# GBA_Wireless_Gamepad.net
KiCad netlist of a schematic drawn in EAGLE
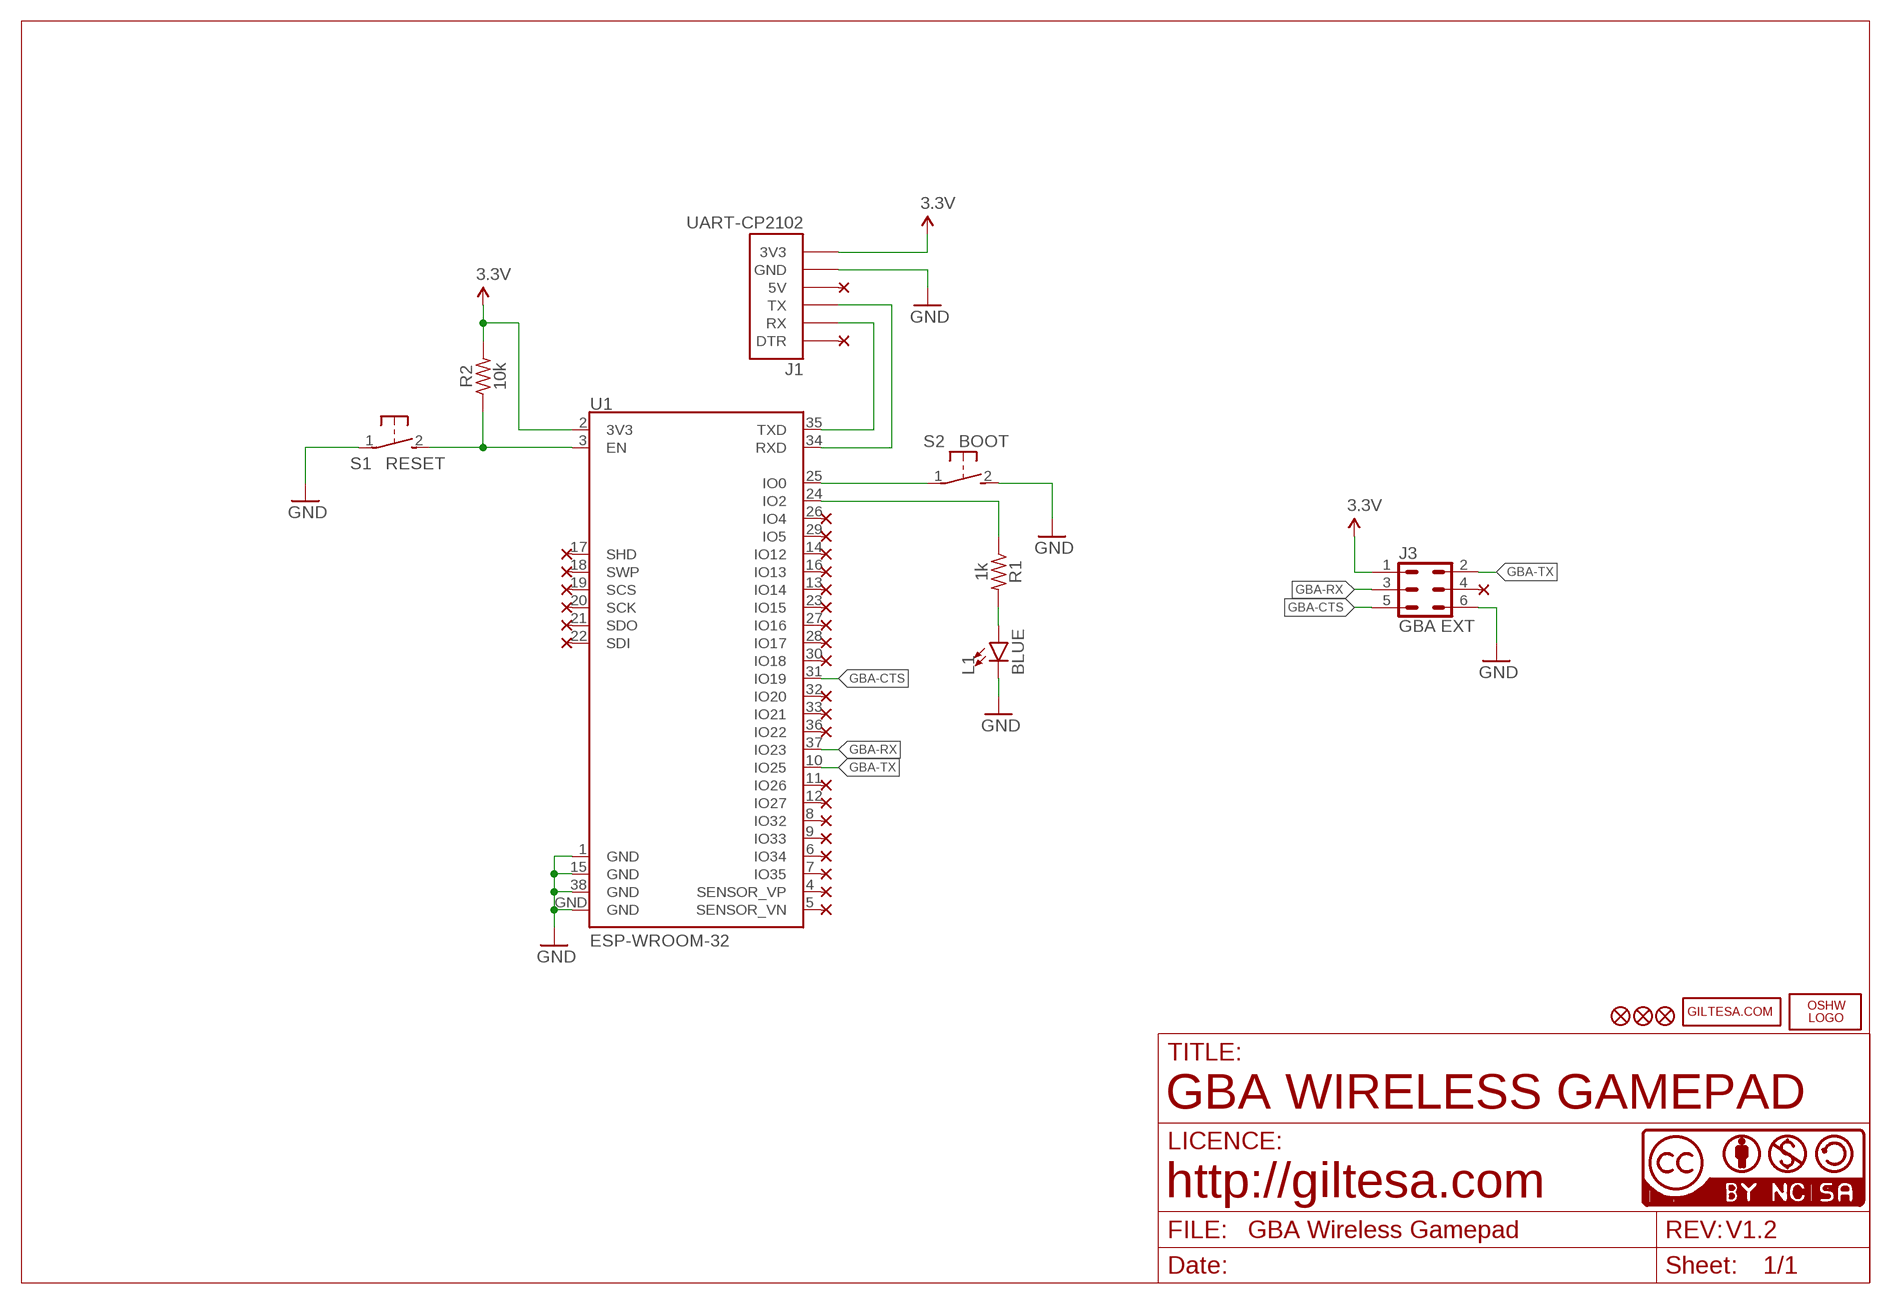
[diagram p0: schematic, sheet 1]

(export (version "E")
  (design (tool "Eeschema 10.0.6"))
  (components
    (comp (ref "J1")
      (value "UART-CP2102")
      (footprint "eagle-import:UART-CP2102")
      (libsource (lib "eagle-import") (part "UART-CP2102"))
    )
    (comp (ref "J3")
      (value "GBA EXT")
      (footprint "eagle-import:GBA_EXT")
      (libsource (lib "eagle-import") (part "GBA_EXT"))
    )
    (comp (ref "L1")
      (value "BLUE")
      (footprint "eagle-import:LED-0603")
      (libsource (lib "eagle-import") (part "LED-BLUE0603"))
    )
    (comp (ref "LOGO1")
      (value "OSHW_LOGO_FILLX0150-NT")
      (footprint "eagle-import:OSHW_FILLX150_NOTEXT")
      (libsource (lib "eagle-import") (part "OSHW_LOGO_FILLX0150-NT"))
    )
    (comp (ref "R1")
      (value "1k")
      (footprint "eagle-import:R0603")
      (libsource (lib "eagle-import") (part "R0603"))
    )
    (comp (ref "R2")
      (value "10k")
      (footprint "eagle-import:R0603")
      (libsource (lib "eagle-import") (part "R0603"))
    )
    (comp (ref "S1")
      (value "RESET")
      (footprint "eagle-import:SWITCH_SMD_4.6X2.8MM")
      (libsource (lib "eagle-import") (part "SWITCH_2P4.6X2.8MM"))
    )
    (comp (ref "S2")
      (value "BOOT")
      (footprint "eagle-import:SWITCH_SMD_4.6X2.8MM")
      (libsource (lib "eagle-import") (part "SWITCH_2P4.6X2.8MM"))
    )
    (comp (ref "U$6")
      (value "FIDUCIAL1X2")
      (footprint "eagle-import:FIDUCIAL-1X2")
      (libsource (lib "eagle-import") (part "FIDUCIAL1X2"))
    )
    (comp (ref "U$7")
      (value "FIDUCIAL1X2")
      (footprint "eagle-import:FIDUCIAL-1X2")
      (libsource (lib "eagle-import") (part "FIDUCIAL1X2"))
    )
    (comp (ref "U$10")
      (value "GILTESA.COM_MASK")
      (footprint "eagle-import:GILTESA.COM_MASK_15MM")
      (libsource (lib "eagle-import") (part "GILTESA.COM_MASK"))
    )
    (comp (ref "U$14")
      (value "FIDUCIAL1X2")
      (footprint "eagle-import:FIDUCIAL-1X2")
      (libsource (lib "eagle-import") (part "FIDUCIAL1X2"))
    )
    (comp (ref "U$17")
      (value "CC-NC-BCNIX")
      (footprint "eagle-import:CC-NC-B_NIX")
      (libsource (lib "eagle-import") (part "CC-NC-BCNIX"))
    )
    (comp (ref "U1")
      (value "ESP-WROOM-32")
      (footprint "eagle-import:ESP32-WROOM-NARROW")
      (libsource (lib "eagle-import") (part "ESP32-WROOMNARROW"))
    )
  )
  (nets
    (net (code "1") (name "3.3V") (class "Default")
      (node (ref "J1") (pin "3V3") (pinfunction "3V3_3V3") (pintype "bidirectional"))
      (node (ref "J3") (pin "1") (pinfunction "1_1") (pintype "passive"))
      (node (ref "R2") (pin "2") (pinfunction "2_2") (pintype "passive"))
      (node (ref "U1") (pin "2") (pinfunction "3V3_2") (pintype "bidirectional"))
    )
    (net (code "2") (name "GBA-CTS") (class "Default")
      (node (ref "J3") (pin "5") (pinfunction "5_5") (pintype "passive"))
      (node (ref "U1") (pin "31") (pinfunction "IO19_31") (pintype "bidirectional"))
    )
    (net (code "3") (name "GBA-RX") (class "Default")
      (node (ref "J3") (pin "3") (pinfunction "3_3") (pintype "passive"))
      (node (ref "U1") (pin "37") (pinfunction "IO23_37") (pintype "bidirectional"))
    )
    (net (code "4") (name "GBA-TX") (class "Default")
      (node (ref "J3") (pin "2") (pinfunction "2_2") (pintype "passive"))
      (node (ref "U1") (pin "10") (pinfunction "IO25_10") (pintype "bidirectional"))
    )
    (net (code "5") (name "GND") (class "Default")
      (node (ref "J1") (pin "GND") (pinfunction "GND_GND") (pintype "bidirectional"))
      (node (ref "J3") (pin "6") (pinfunction "6_6") (pintype "passive"))
      (node (ref "L1") (pin "C") (pinfunction "C_C") (pintype "passive"))
      (node (ref "S1") (pin "1") (pinfunction "A_1") (pintype "passive"))
      (node (ref "S2") (pin "2") (pinfunction "B_2") (pintype "passive"))
      (node (ref "U1") (pin "1") (pinfunction "GND_1") (pintype "bidirectional"))
      (node (ref "U1") (pin "15") (pinfunction "GND_15") (pintype "bidirectional"))
      (node (ref "U1") (pin "38") (pinfunction "GND_38") (pintype "bidirectional"))
      (node (ref "U1") (pin "GND") (pinfunction "GND_GND") (pintype "bidirectional"))
    )
    (net (code "6") (name "Net-(L1-PadA)") (class "Default")
      (node (ref "L1") (pin "A") (pinfunction "A_A") (pintype "passive"))
      (node (ref "R1") (pin "2") (pinfunction "2_2") (pintype "passive"))
    )
    (net (code "7") (name "Net-(S1-B)") (class "Default")
      (node (ref "R2") (pin "1") (pinfunction "1_1") (pintype "passive"))
      (node (ref "S1") (pin "2") (pinfunction "B_2") (pintype "passive"))
      (node (ref "U1") (pin "3") (pinfunction "EN_3") (pintype "bidirectional"))
    )
    (net (code "8") (name "Net-(S2-A)") (class "Default")
      (node (ref "S2") (pin "1") (pinfunction "A_1") (pintype "passive"))
      (node (ref "U1") (pin "25") (pinfunction "IO0_25") (pintype "bidirectional"))
    )
    (net (code "9") (name "Net-(U1-IO2)") (class "Default")
      (node (ref "R1") (pin "1") (pinfunction "1_1") (pintype "passive"))
      (node (ref "U1") (pin "24") (pinfunction "IO2_24") (pintype "bidirectional"))
    )
    (net (code "10") (name "Net-(U1-RXD)") (class "Default")
      (node (ref "J1") (pin "TX") (pinfunction "TX_TX") (pintype "bidirectional"))
      (node (ref "U1") (pin "34") (pinfunction "RXD_34") (pintype "bidirectional"))
    )
    (net (code "11") (name "Net-(U1-TXD)") (class "Default")
      (node (ref "J1") (pin "RX") (pinfunction "RX_RX") (pintype "bidirectional"))
      (node (ref "U1") (pin "35") (pinfunction "TXD_35") (pintype "bidirectional"))
    )
    (net (code "12") (name "unconnected-(J1-Pad5V)") (class "Default")
      (node (ref "J1") (pin "5V") (pinfunction "5V_5V") (pintype "bidirectional"))
    )
    (net (code "13") (name "unconnected-(J1-PadDTR)") (class "Default")
      (node (ref "J1") (pin "DTR") (pinfunction "DTR_DTR") (pintype "bidirectional"))
    )
    (net (code "14") (name "unconnected-(J3-Pad4)") (class "Default")
      (node (ref "J3") (pin "4") (pinfunction "4_4") (pintype "passive"))
    )
    (net (code "15") (name "unconnected-(U1-IO4-Pad26)") (class "Default")
      (node (ref "U1") (pin "26") (pinfunction "IO4_26") (pintype "bidirectional"))
    )
    (net (code "16") (name "unconnected-(U1-IO5-Pad29)") (class "Default")
      (node (ref "U1") (pin "29") (pinfunction "IO5_29") (pintype "bidirectional"))
    )
    (net (code "17") (name "unconnected-(U1-IO12-Pad14)") (class "Default")
      (node (ref "U1") (pin "14") (pinfunction "IO12_14") (pintype "bidirectional"))
    )
    (net (code "18") (name "unconnected-(U1-IO13-Pad16)") (class "Default")
      (node (ref "U1") (pin "16") (pinfunction "IO13_16") (pintype "bidirectional"))
    )
    (net (code "19") (name "unconnected-(U1-IO14-Pad13)") (class "Default")
      (node (ref "U1") (pin "13") (pinfunction "IO14_13") (pintype "bidirectional"))
    )
    (net (code "20") (name "unconnected-(U1-IO15-Pad23)") (class "Default")
      (node (ref "U1") (pin "23") (pinfunction "IO15_23") (pintype "bidirectional"))
    )
    (net (code "21") (name "unconnected-(U1-IO16-Pad27)") (class "Default")
      (node (ref "U1") (pin "27") (pinfunction "IO16_27") (pintype "bidirectional"))
    )
    (net (code "22") (name "unconnected-(U1-IO17-Pad28)") (class "Default")
      (node (ref "U1") (pin "28") (pinfunction "IO17_28") (pintype "bidirectional"))
    )
    (net (code "23") (name "unconnected-(U1-IO18-Pad30)") (class "Default")
      (node (ref "U1") (pin "30") (pinfunction "IO18_30") (pintype "bidirectional"))
    )
    (net (code "24") (name "unconnected-(U1-IO20-Pad32)") (class "Default")
      (node (ref "U1") (pin "32") (pinfunction "IO20_32") (pintype "bidirectional"))
    )
    (net (code "25") (name "unconnected-(U1-IO21-Pad33)") (class "Default")
      (node (ref "U1") (pin "33") (pinfunction "IO21_33") (pintype "bidirectional"))
    )
    (net (code "26") (name "unconnected-(U1-IO22-Pad36)") (class "Default")
      (node (ref "U1") (pin "36") (pinfunction "IO22_36") (pintype "bidirectional"))
    )
    (net (code "27") (name "unconnected-(U1-IO26-Pad11)") (class "Default")
      (node (ref "U1") (pin "11") (pinfunction "IO26_11") (pintype "bidirectional"))
    )
    (net (code "28") (name "unconnected-(U1-IO27-Pad12)") (class "Default")
      (node (ref "U1") (pin "12") (pinfunction "IO27_12") (pintype "bidirectional"))
    )
    (net (code "29") (name "unconnected-(U1-IO32-Pad8)") (class "Default")
      (node (ref "U1") (pin "8") (pinfunction "IO32_8") (pintype "bidirectional"))
    )
    (net (code "30") (name "unconnected-(U1-IO33-Pad9)") (class "Default")
      (node (ref "U1") (pin "9") (pinfunction "IO33_9") (pintype "bidirectional"))
    )
    (net (code "31") (name "unconnected-(U1-IO34-Pad6)") (class "Default")
      (node (ref "U1") (pin "6") (pinfunction "IO34_6") (pintype "bidirectional"))
    )
    (net (code "32") (name "unconnected-(U1-IO35-Pad7)") (class "Default")
      (node (ref "U1") (pin "7") (pinfunction "IO35_7") (pintype "bidirectional"))
    )
    (net (code "33") (name "unconnected-(U1-SCK-Pad20)") (class "Default")
      (node (ref "U1") (pin "20") (pinfunction "SCK_20") (pintype "bidirectional"))
    )
    (net (code "34") (name "unconnected-(U1-SCS-Pad19)") (class "Default")
      (node (ref "U1") (pin "19") (pinfunction "SCS_19") (pintype "bidirectional"))
    )
    (net (code "35") (name "unconnected-(U1-SDI-Pad22)") (class "Default")
      (node (ref "U1") (pin "22") (pinfunction "SDI_22") (pintype "bidirectional"))
    )
    (net (code "36") (name "unconnected-(U1-SDO-Pad21)") (class "Default")
      (node (ref "U1") (pin "21") (pinfunction "SDO_21") (pintype "bidirectional"))
    )
    (net (code "37") (name "unconnected-(U1-SENSOR_VN-Pad5)") (class "Default")
      (node (ref "U1") (pin "5") (pinfunction "SENSOR_VN_5") (pintype "bidirectional"))
    )
    (net (code "38") (name "unconnected-(U1-SENSOR_VP-Pad4)") (class "Default")
      (node (ref "U1") (pin "4") (pinfunction "SENSOR_VP_4") (pintype "bidirectional"))
    )
    (net (code "39") (name "unconnected-(U1-SHD-Pad17)") (class "Default")
      (node (ref "U1") (pin "17") (pinfunction "SHD_17") (pintype "bidirectional"))
    )
    (net (code "40") (name "unconnected-(U1-SWP-Pad18)") (class "Default")
      (node (ref "U1") (pin "18") (pinfunction "SWP_18") (pintype "bidirectional"))
    )
  )
)
